# Node.net
KiCad netlist of a schematic drawn in EAGLE
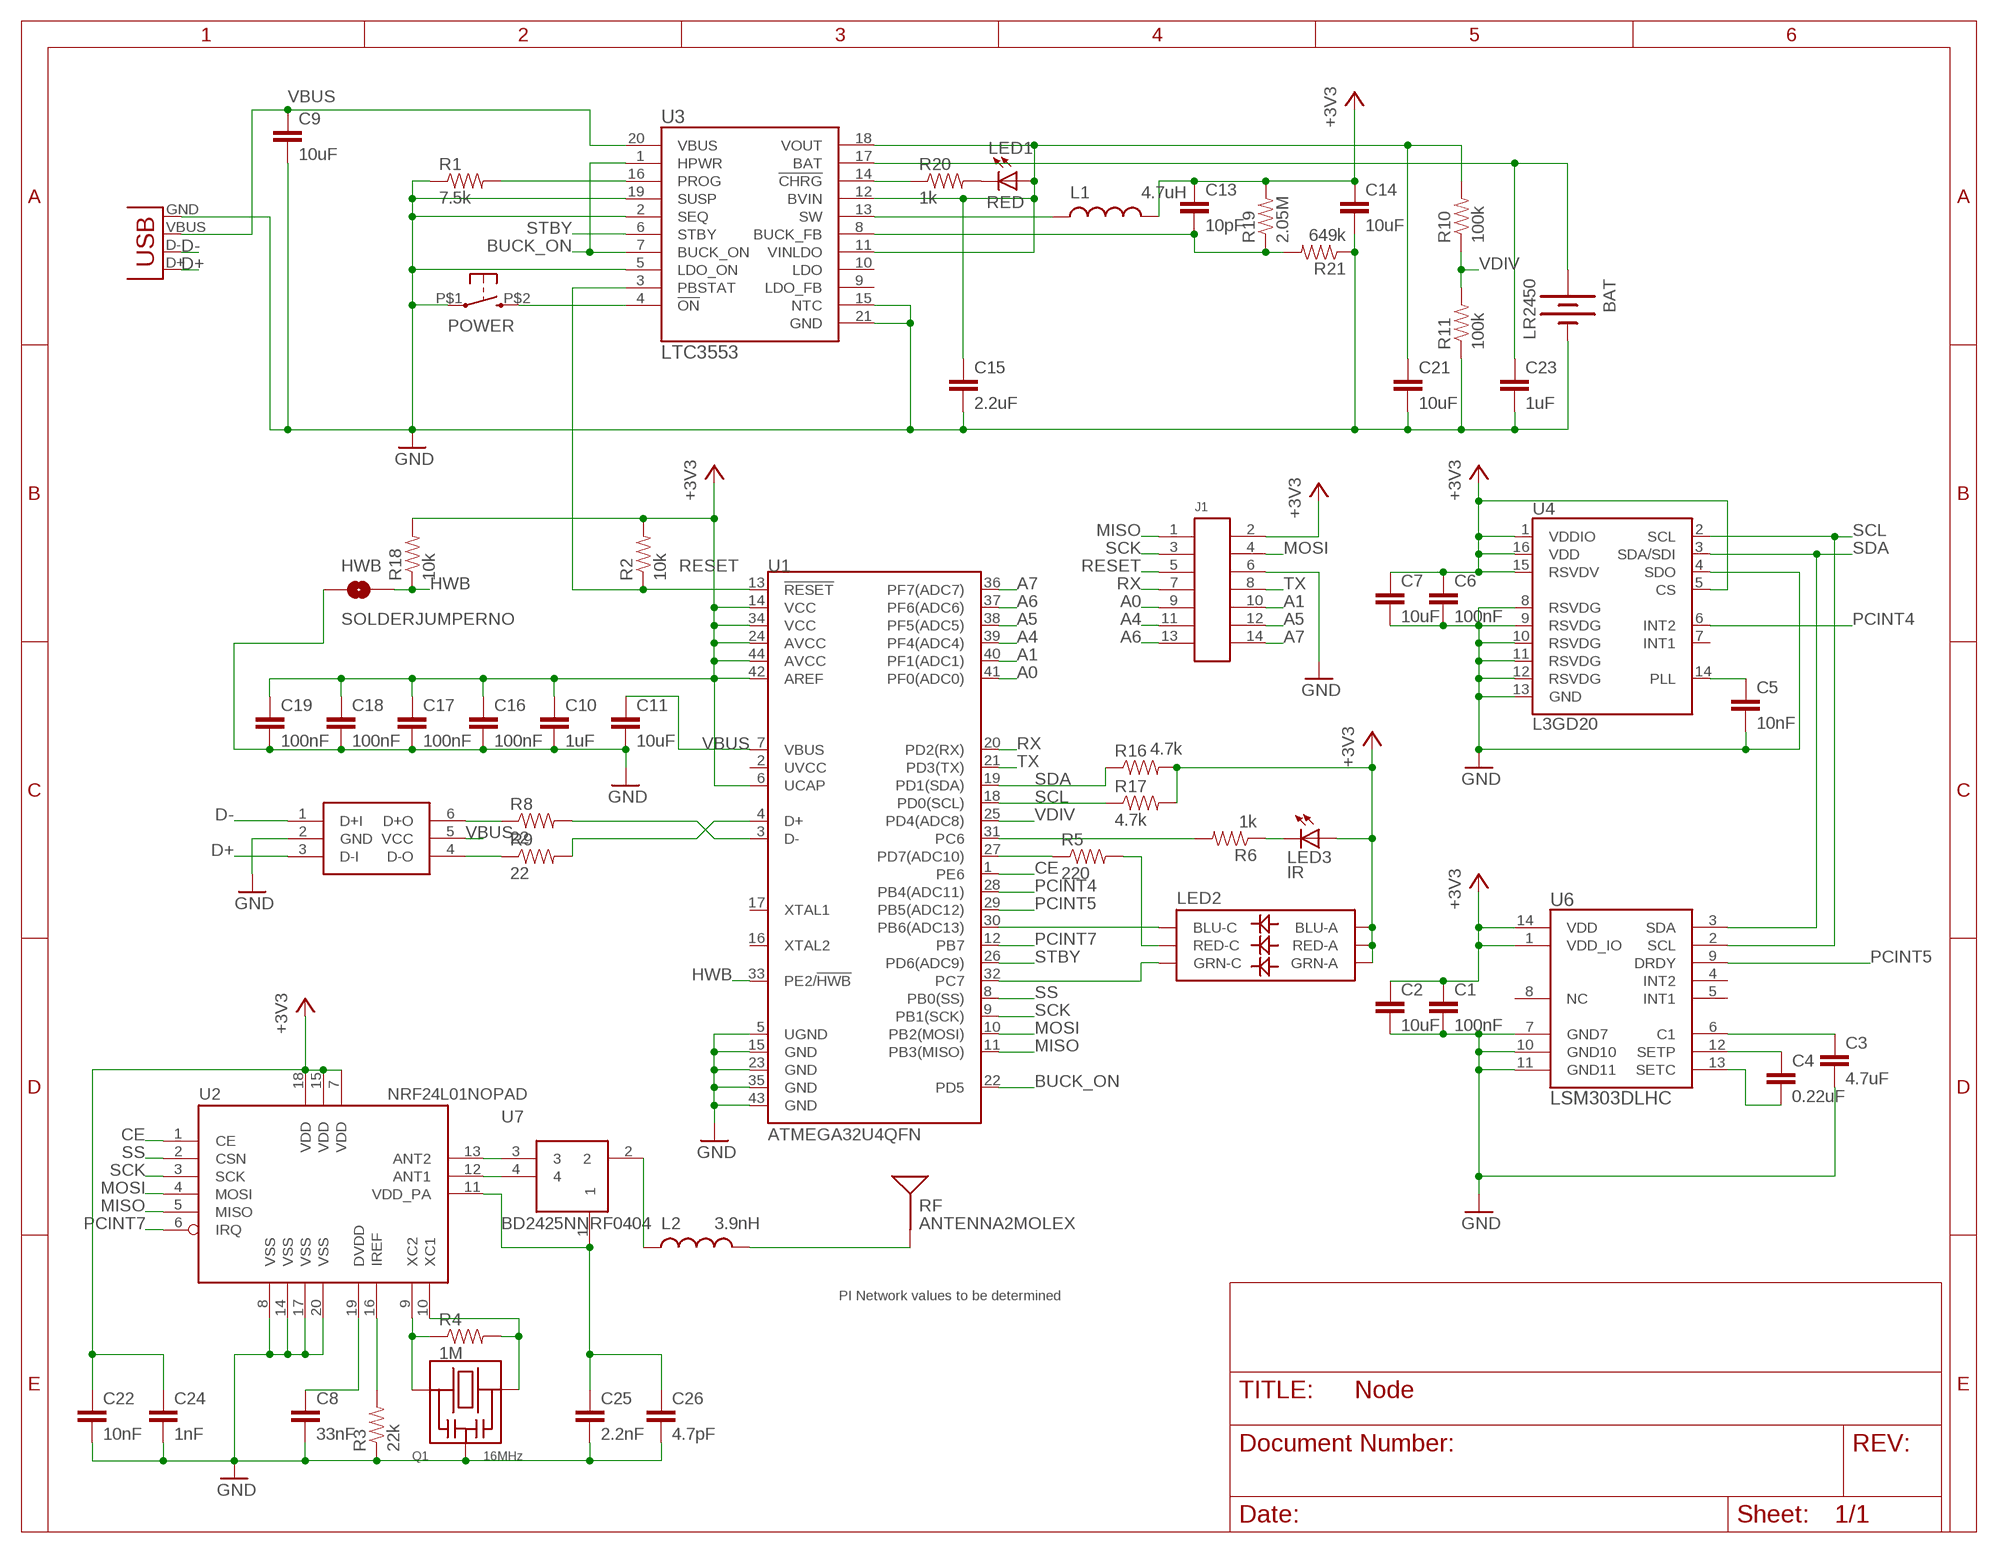
[diagram p0: schematic, sheet 1]

(export (version "E")
  (design (tool "Eeschema 10.0.6"))
  (components
    (comp (ref "BAT")
      (value "LR2450")
      (footprint "eagle-import:BATTCON_245MM_SLOT")
      (libsource (lib "eagle-import") (part "BATTERYSLOT"))
    )
    (comp (ref "C1")
      (value "100nF")
      (footprint "eagle-import:0402-CAP")
      (libsource (lib "eagle-import") (part "CAP0402-CAP"))
    )
    (comp (ref "C2")
      (value "10uF")
      (footprint "eagle-import:0603-CAP")
      (libsource (lib "eagle-import") (part "CAP0603-CAP"))
    )
    (comp (ref "C3")
      (value "4.7uF")
      (footprint "eagle-import:0603-CAP")
      (libsource (lib "eagle-import") (part "CAP0603-CAP"))
    )
    (comp (ref "C4")
      (value "0.22uF")
      (footprint "eagle-import:0402-CAP")
      (libsource (lib "eagle-import") (part "CAP0402-CAP"))
    )
    (comp (ref "C5")
      (value "10nF")
      (footprint "eagle-import:0402-CAP")
      (libsource (lib "eagle-import") (part "CAP0402-CAP"))
    )
    (comp (ref "C6")
      (value "100nF")
      (footprint "eagle-import:0402-CAP")
      (libsource (lib "eagle-import") (part "CAP0402-CAP"))
    )
    (comp (ref "C7")
      (value "10uF")
      (footprint "eagle-import:0603-CAP")
      (libsource (lib "eagle-import") (part "CAP0603-CAP"))
    )
    (comp (ref "C8")
      (value "33nF")
      (footprint "eagle-import:0402-CAP")
      (libsource (lib "eagle-import") (part "CAP0402-CAP"))
    )
    (comp (ref "C9")
      (value "10uF")
      (footprint "eagle-import:0603-CAP")
      (libsource (lib "eagle-import") (part "CAP0603-CAP"))
    )
    (comp (ref "C10")
      (value "1uF")
      (footprint "eagle-import:0402-CAP")
      (libsource (lib "eagle-import") (part "CAP0402-CAP"))
    )
    (comp (ref "C11")
      (value "10uF")
      (footprint "eagle-import:0603-CAP")
      (libsource (lib "eagle-import") (part "CAP0603-CAP"))
    )
    (comp (ref "C13")
      (value "10pF")
      (footprint "eagle-import:0402-CAP")
      (libsource (lib "eagle-import") (part "CAP0402-CAP"))
    )
    (comp (ref "C14")
      (value "10uF")
      (footprint "eagle-import:0603-CAP")
      (libsource (lib "eagle-import") (part "CAP0603-CAP"))
    )
    (comp (ref "C15")
      (value "2.2uF")
      (footprint "eagle-import:0402-CAP")
      (libsource (lib "eagle-import") (part "CAP0402-CAP"))
    )
    (comp (ref "C16")
      (value "100nF")
      (footprint "eagle-import:0402-CAP")
      (libsource (lib "eagle-import") (part "CAP0402-CAP"))
    )
    (comp (ref "C17")
      (value "100nF")
      (footprint "eagle-import:0402-CAP")
      (libsource (lib "eagle-import") (part "CAP0402-CAP"))
    )
    (comp (ref "C18")
      (value "100nF")
      (footprint "eagle-import:0402-CAP")
      (libsource (lib "eagle-import") (part "CAP0402-CAP"))
    )
    (comp (ref "C19")
      (value "100nF")
      (footprint "eagle-import:0402-CAP")
      (libsource (lib "eagle-import") (part "CAP0402-CAP"))
    )
    (comp (ref "C21")
      (value "10uF")
      (footprint "eagle-import:0603-CAP")
      (libsource (lib "eagle-import") (part "CAP0603-CAP"))
    )
    (comp (ref "C22")
      (value "10nF")
      (footprint "eagle-import:0402-CAP")
      (libsource (lib "eagle-import") (part "CAP0402-CAP"))
    )
    (comp (ref "C23")
      (value "1uF")
      (footprint "eagle-import:0402-CAP")
      (libsource (lib "eagle-import") (part "CAP0402-CAP"))
    )
    (comp (ref "C24")
      (value "1nF")
      (footprint "eagle-import:0402-CAP")
      (libsource (lib "eagle-import") (part "CAP0402-CAP"))
    )
    (comp (ref "C25")
      (value "2.2nF")
      (footprint "eagle-import:0402-CAP")
      (libsource (lib "eagle-import") (part "CAP0402-CAP"))
    )
    (comp (ref "C26")
      (value "4.7pF")
      (footprint "eagle-import:0402-CAP")
      (libsource (lib "eagle-import") (part "CAP0402-CAP"))
    )
    (comp (ref "HWB")
      (value "SOLDERJUMPERNO")
      (footprint "eagle-import:SJ_2S-NO")
      (libsource (lib "eagle-import") (part "SOLDERJUMPERNO"))
    )
    (comp (ref "J1")
      (value "DF12A3.0-14DS")
      (footprint "eagle-import:DF12A3.0-14DS")
      (libsource (lib "eagle-import") (part "DF12A3.0-14DS"))
    )
    (comp (ref "L1")
      (value "4.7uH")
      (footprint "eagle-import:VLS30")
      (libsource (lib "eagle-import") (part "INDUCTORVLS30"))
    )
    (comp (ref "L2")
      (value "3.9nH")
      (footprint "eagle-import:C0402")
      (libsource (lib "eagle-import") (part "INDUCTOR0402"))
    )
    (comp (ref "LED1")
      (value "RED")
      (footprint "eagle-import:LED-0603")
      (libsource (lib "eagle-import") (part "LED0603"))
    )
    (comp (ref "LED2")
      (value "LED-TRICOLOR-5050LED-TRICOLOR-0606")
      (footprint "eagle-import:0606")
      (libsource (lib "eagle-import") (part "LED-TRICOLOR-5050LED-TRICOLOR-0606"))
    )
    (comp (ref "LED3")
      (value "IR")
      (footprint "eagle-import:LED-0603")
      (libsource (lib "eagle-import") (part "LED0603"))
    )
    (comp (ref "POWER")
      (value "KSS")
      (footprint "eagle-import:KSS")
      (libsource (lib "eagle-import") (part "KSS"))
    )
    (comp (ref "Q1")
      (value "16MHz")
      (footprint "eagle-import:PRQC")
      (libsource (lib "eagle-import") (part "RESONATORPRQC"))
    )
    (comp (ref "R1")
      (value "7.5k")
      (footprint "eagle-import:0402-RES")
      (libsource (lib "eagle-import") (part "RESISTOR0402-RES"))
    )
    (comp (ref "R2")
      (value "10k")
      (footprint "eagle-import:0402-RES")
      (libsource (lib "eagle-import") (part "RESISTOR0402-RES"))
    )
    (comp (ref "R3")
      (value "22k")
      (footprint "eagle-import:0402-RES")
      (libsource (lib "eagle-import") (part "RESISTOR0402-RES"))
    )
    (comp (ref "R4")
      (value "1M")
      (footprint "eagle-import:0402-RES")
      (libsource (lib "eagle-import") (part "RESISTOR0402-RES"))
    )
    (comp (ref "R5")
      (value "220")
      (footprint "eagle-import:0402-RES")
      (libsource (lib "eagle-import") (part "RESISTOR0402-RES"))
    )
    (comp (ref "R6")
      (value "1k")
      (footprint "eagle-import:0402-RES")
      (libsource (lib "eagle-import") (part "RESISTOR0402-RES"))
    )
    (comp (ref "R8")
      (value "22")
      (footprint "eagle-import:0402-RES")
      (libsource (lib "eagle-import") (part "RESISTOR0402-RES"))
    )
    (comp (ref "R9")
      (value "22")
      (footprint "eagle-import:0402-RES")
      (libsource (lib "eagle-import") (part "RESISTOR0402-RES"))
    )
    (comp (ref "R10")
      (value "100k")
      (footprint "eagle-import:0402-RES")
      (libsource (lib "eagle-import") (part "RESISTOR0402-RES"))
    )
    (comp (ref "R11")
      (value "100k")
      (footprint "eagle-import:0402-RES")
      (libsource (lib "eagle-import") (part "RESISTOR0402-RES"))
    )
    (comp (ref "R16")
      (value "4.7k")
      (footprint "eagle-import:0402-RES")
      (libsource (lib "eagle-import") (part "RESISTOR0402-RES"))
    )
    (comp (ref "R17")
      (value "4.7k")
      (footprint "eagle-import:0402-RES")
      (libsource (lib "eagle-import") (part "RESISTOR0402-RES"))
    )
    (comp (ref "R18")
      (value "10k")
      (footprint "eagle-import:0402-RES")
      (libsource (lib "eagle-import") (part "RESISTOR0402-RES"))
    )
    (comp (ref "R19")
      (value "2.05M")
      (footprint "eagle-import:0402-RES")
      (libsource (lib "eagle-import") (part "RESISTOR0402-RES"))
    )
    (comp (ref "R20")
      (value "1k")
      (footprint "eagle-import:0402-RES")
      (libsource (lib "eagle-import") (part "RESISTOR0402-RES"))
    )
    (comp (ref "R21")
      (value "649k")
      (footprint "eagle-import:0402-RES")
      (libsource (lib "eagle-import") (part "RESISTOR0402-RES"))
    )
    (comp (ref "RF")
      (value "ANTENNA2MOLEX")
      (footprint "eagle-import:MOLEX2.4SMD")
      (libsource (lib "eagle-import") (part "ANTENNA2MOLEX"))
    )
    (comp (ref "U1")
      (value "ATMEGA32U4QFN")
      (footprint "eagle-import:QFN-44")
      (libsource (lib "eagle-import") (part "ATMEGA32U4QFN"))
    )
    (comp (ref "U2")
      (value "NRF24L01NOPAD")
      (footprint "eagle-import:QFN20-NOPAD")
      (libsource (lib "eagle-import") (part "NRF24L01NOPAD"))
    )
    (comp (ref "U3")
      (value "LTC3553")
      (footprint "eagle-import:QFN20-3X3")
      (libsource (lib "eagle-import") (part "LTC3553"))
    )
    (comp (ref "U4")
      (value "L3GD20")
      (footprint "eagle-import:LGA16-4X4")
      (libsource (lib "eagle-import") (part "L3GD20"))
    )
    (comp (ref "U6")
      (value "LSM303DLHC")
      (footprint "eagle-import:LGA14-3X5")
      (libsource (lib "eagle-import") (part "LSM303DLHC"))
    )
    (comp (ref "U7")
      (value "BD2425NNRF0404")
      (footprint "eagle-import:BD2425NNRF")
      (libsource (lib "eagle-import") (part "BD2425NNRF0404"))
    )
    (comp (ref "U9")
      (value "RCLAMP0502A")
      (footprint "eagle-import:SOT-666")
      (libsource (lib "eagle-import") (part "RCLAMP0502A"))
    )
    (comp (ref "X1")
      (value "USB-FCI")
      (footprint "eagle-import:USB-MICROB-FCI")
      (libsource (lib "eagle-import") (part "USB-FCI"))
    )
  )
  (nets
    (net (code "1") (name "+3V3") (class "Default")
      (node (ref "C1") (pin "1") (pinfunction "1_1") (pintype "passive"))
      (node (ref "C10") (pin "1") (pinfunction "1_1") (pintype "passive"))
      (node (ref "C13") (pin "1") (pinfunction "1_1") (pintype "passive"))
      (node (ref "C14") (pin "1") (pinfunction "1_1") (pintype "passive"))
      (node (ref "C16") (pin "1") (pinfunction "1_1") (pintype "passive"))
      (node (ref "C17") (pin "1") (pinfunction "1_1") (pintype "passive"))
      (node (ref "C18") (pin "1") (pinfunction "1_1") (pintype "passive"))
      (node (ref "C19") (pin "1") (pinfunction "1_1") (pintype "passive"))
      (node (ref "C2") (pin "1") (pinfunction "1_1") (pintype "passive"))
      (node (ref "C22") (pin "1") (pinfunction "1_1") (pintype "passive"))
      (node (ref "C24") (pin "1") (pinfunction "1_1") (pintype "passive"))
      (node (ref "C6") (pin "1") (pinfunction "1_1") (pintype "passive"))
      (node (ref "C7") (pin "1") (pinfunction "1_1") (pintype "passive"))
      (node (ref "J1") (pin "2") (pinfunction "2_2") (pintype "bidirectional"))
      (node (ref "L1") (pin "2") (pinfunction "2_2") (pintype "passive"))
      (node (ref "LED2") (pin "4") (pinfunction "BLU-A_4") (pintype "bidirectional"))
      (node (ref "LED2") (pin "5") (pinfunction "RED-A_5") (pintype "bidirectional"))
      (node (ref "LED2") (pin "6") (pinfunction "GRN-A_6") (pintype "bidirectional"))
      (node (ref "LED3") (pin "A") (pinfunction "A_A") (pintype "passive"))
      (node (ref "R16") (pin "2") (pinfunction "2_2") (pintype "passive"))
      (node (ref "R17") (pin "2") (pinfunction "2_2") (pintype "passive"))
      (node (ref "R18") (pin "2") (pinfunction "2_2") (pintype "passive"))
      (node (ref "R19") (pin "2") (pinfunction "2_2") (pintype "passive"))
      (node (ref "R2") (pin "2") (pinfunction "2_2") (pintype "passive"))
      (node (ref "U1") (pin "14") (pinfunction "VCC_14") (pintype "bidirectional"))
      (node (ref "U1") (pin "24") (pinfunction "AVCC_24") (pintype "bidirectional"))
      (node (ref "U1") (pin "34") (pinfunction "VCC_34") (pintype "bidirectional"))
      (node (ref "U1") (pin "42") (pinfunction "AREF_42") (pintype "bidirectional"))
      (node (ref "U1") (pin "44") (pinfunction "AVCC_44") (pintype "bidirectional"))
      (node (ref "U1") (pin "6") (pinfunction "UCAP_6") (pintype "bidirectional"))
      (node (ref "U2") (pin "15") (pinfunction "VDD_15") (pintype "power_in"))
      (node (ref "U2") (pin "18") (pinfunction "VDD_18") (pintype "power_in"))
      (node (ref "U2") (pin "7") (pinfunction "VDD_7") (pintype "power_in"))
      (node (ref "U4") (pin "1") (pinfunction "VDDIO_1") (pintype "bidirectional"))
      (node (ref "U4") (pin "15") (pinfunction "RSVDV_15") (pintype "bidirectional"))
      (node (ref "U4") (pin "16") (pinfunction "VDD_16") (pintype "bidirectional"))
      (node (ref "U4") (pin "5") (pinfunction "CS_5") (pintype "bidirectional"))
      (node (ref "U6") (pin "1") (pinfunction "VDD_IO_1") (pintype "bidirectional"))
      (node (ref "U6") (pin "14") (pinfunction "VDD_14") (pintype "bidirectional"))
    )
    (net (code "2") (name "/A0") (class "Default")
      (node (ref "J1") (pin "9") (pinfunction "9_9") (pintype "bidirectional"))
      (node (ref "U1") (pin "41") (pinfunction "PF0(ADC0)_41") (pintype "bidirectional"))
    )
    (net (code "3") (name "/A1") (class "Default")
      (node (ref "J1") (pin "10") (pinfunction "10_10") (pintype "bidirectional"))
      (node (ref "U1") (pin "40") (pinfunction "PF1(ADC1)_40") (pintype "bidirectional"))
    )
    (net (code "4") (name "/A4") (class "Default")
      (node (ref "J1") (pin "11") (pinfunction "11_11") (pintype "bidirectional"))
      (node (ref "U1") (pin "39") (pinfunction "PF4(ADC4)_39") (pintype "bidirectional"))
    )
    (net (code "5") (name "/A5") (class "Default")
      (node (ref "J1") (pin "12") (pinfunction "12_12") (pintype "bidirectional"))
      (node (ref "U1") (pin "38") (pinfunction "PF5(ADC5)_38") (pintype "bidirectional"))
    )
    (net (code "6") (name "/A6") (class "Default")
      (node (ref "J1") (pin "13") (pinfunction "13_13") (pintype "bidirectional"))
      (node (ref "U1") (pin "37") (pinfunction "PF6(ADC6)_37") (pintype "bidirectional"))
    )
    (net (code "7") (name "/A7") (class "Default")
      (node (ref "J1") (pin "14") (pinfunction "14_14") (pintype "bidirectional"))
      (node (ref "U1") (pin "36") (pinfunction "PF7(ADC7)_36") (pintype "bidirectional"))
    )
    (net (code "8") (name "/BUCK_ON") (class "Default")
      (node (ref "U1") (pin "22") (pinfunction "PD5_22") (pintype "bidirectional"))
      (node (ref "U3") (pin "1") (pinfunction "HPWR_1") (pintype "bidirectional"))
      (node (ref "U3") (pin "7") (pinfunction "BUCK_ON_7") (pintype "bidirectional"))
    )
    (net (code "9") (name "/CE") (class "Default")
      (node (ref "U1") (pin "1") (pinfunction "PE6_1") (pintype "bidirectional"))
      (node (ref "U2") (pin "1") (pinfunction "CE_1") (pintype "input"))
    )
    (net (code "10") (name "/D+") (class "Default")
      (node (ref "U9") (pin "3") (pinfunction "D-I_3") (pintype "bidirectional"))
      (node (ref "X1") (pin "D+") (pinfunction "D+_D+") (pintype "bidirectional"))
    )
    (net (code "11") (name "/D-") (class "Default")
      (node (ref "U9") (pin "1") (pinfunction "D+I_1") (pintype "bidirectional"))
      (node (ref "X1") (pin "D-") (pinfunction "D-_D-") (pintype "bidirectional"))
    )
    (net (code "12") (name "/HWB") (class "Default")
      (node (ref "HWB") (pin "2") (pinfunction "2_2") (pintype "passive"))
      (node (ref "R18") (pin "1") (pinfunction "1_1") (pintype "passive"))
      (node (ref "U1") (pin "33") (pinfunction "PE2/~{HWB}_33") (pintype "bidirectional"))
    )
    (net (code "13") (name "/MISO") (class "Default")
      (node (ref "J1") (pin "1") (pinfunction "1_1") (pintype "bidirectional"))
      (node (ref "U1") (pin "11") (pinfunction "PB3(MISO)_11") (pintype "bidirectional"))
      (node (ref "U2") (pin "5") (pinfunction "MISO_5") (pintype "output"))
    )
    (net (code "14") (name "/MOSI") (class "Default")
      (node (ref "J1") (pin "4") (pinfunction "4_4") (pintype "bidirectional"))
      (node (ref "U1") (pin "10") (pinfunction "PB2(MOSI)_10") (pintype "bidirectional"))
      (node (ref "U2") (pin "4") (pinfunction "MOSI_4") (pintype "input"))
    )
    (net (code "15") (name "/PCINT4") (class "Default")
      (node (ref "U1") (pin "28") (pinfunction "PB4(ADC11)_28") (pintype "bidirectional"))
      (node (ref "U4") (pin "6") (pinfunction "INT2_6") (pintype "bidirectional"))
    )
    (net (code "16") (name "/PCINT5") (class "Default")
      (node (ref "U1") (pin "29") (pinfunction "PB5(ADC12)_29") (pintype "bidirectional"))
      (node (ref "U6") (pin "9") (pinfunction "DRDY_9") (pintype "bidirectional"))
    )
    (net (code "17") (name "/PCINT7") (class "Default")
      (node (ref "U1") (pin "12") (pinfunction "PB7_12") (pintype "bidirectional"))
      (node (ref "U2") (pin "6") (pinfunction "IRQ_6") (pintype "output"))
    )
    (net (code "18") (name "/RESET") (class "Default")
      (node (ref "J1") (pin "5") (pinfunction "5_5") (pintype "bidirectional"))
      (node (ref "R2") (pin "1") (pinfunction "1_1") (pintype "passive"))
      (node (ref "U1") (pin "13") (pinfunction "~{RESET}_13") (pintype "bidirectional"))
      (node (ref "U3") (pin "3") (pinfunction "PBSTAT_3") (pintype "bidirectional"))
    )
    (net (code "19") (name "/RX") (class "Default")
      (node (ref "J1") (pin "7") (pinfunction "7_7") (pintype "bidirectional"))
      (node (ref "U1") (pin "20") (pinfunction "PD2(RX)_20") (pintype "bidirectional"))
    )
    (net (code "20") (name "/SCK") (class "Default")
      (node (ref "J1") (pin "3") (pinfunction "3_3") (pintype "bidirectional"))
      (node (ref "U1") (pin "9") (pinfunction "PB1(SCK)_9") (pintype "bidirectional"))
      (node (ref "U2") (pin "3") (pinfunction "SCK_3") (pintype "input"))
    )
    (net (code "21") (name "/SCL") (class "Default")
      (node (ref "R17") (pin "1") (pinfunction "1_1") (pintype "passive"))
      (node (ref "U1") (pin "18") (pinfunction "PD0(SCL)_18") (pintype "bidirectional"))
      (node (ref "U4") (pin "2") (pinfunction "SCL_2") (pintype "bidirectional"))
      (node (ref "U6") (pin "2") (pinfunction "SCL_2") (pintype "bidirectional"))
    )
    (net (code "22") (name "/SDA") (class "Default")
      (node (ref "R16") (pin "1") (pinfunction "1_1") (pintype "passive"))
      (node (ref "U1") (pin "19") (pinfunction "PD1(SDA)_19") (pintype "bidirectional"))
      (node (ref "U4") (pin "3") (pinfunction "SDA/SDI_3") (pintype "bidirectional"))
      (node (ref "U6") (pin "3") (pinfunction "SDA_3") (pintype "bidirectional"))
    )
    (net (code "23") (name "/SS") (class "Default")
      (node (ref "U1") (pin "8") (pinfunction "PB0(SS)_8") (pintype "bidirectional"))
      (node (ref "U2") (pin "2") (pinfunction "CSN_2") (pintype "input"))
    )
    (net (code "24") (name "/STBY") (class "Default")
      (node (ref "U1") (pin "26") (pinfunction "PD6(ADC9)_26") (pintype "bidirectional"))
      (node (ref "U3") (pin "6") (pinfunction "STBY_6") (pintype "bidirectional"))
    )
    (net (code "25") (name "/TX") (class "Default")
      (node (ref "J1") (pin "8") (pinfunction "8_8") (pintype "bidirectional"))
      (node (ref "U1") (pin "21") (pinfunction "PD3(TX)_21") (pintype "bidirectional"))
    )
    (net (code "26") (name "/VBUS") (class "Default")
      (node (ref "C11") (pin "1") (pinfunction "1_1") (pintype "passive"))
      (node (ref "C9") (pin "1") (pinfunction "1_1") (pintype "passive"))
      (node (ref "U1") (pin "7") (pinfunction "VBUS_7") (pintype "bidirectional"))
      (node (ref "U3") (pin "20") (pinfunction "VBUS_20") (pintype "bidirectional"))
      (node (ref "U9") (pin "5") (pinfunction "VCC_5") (pintype "bidirectional"))
      (node (ref "X1") (pin "VBUS") (pinfunction "VBUS_VBUS") (pintype "bidirectional"))
    )
    (net (code "27") (name "/VDIV") (class "Default")
      (node (ref "R10") (pin "1") (pinfunction "1_1") (pintype "passive"))
      (node (ref "R11") (pin "2") (pinfunction "2_2") (pintype "passive"))
      (node (ref "U1") (pin "25") (pinfunction "PD4(ADC8)_25") (pintype "bidirectional"))
    )
    (net (code "28") (name "GND") (class "Default")
      (node (ref "BAT") (pin "GND") (pinfunction "-_GND") (pintype "power_in"))
      (node (ref "C1") (pin "2") (pinfunction "2_2") (pintype "passive"))
      (node (ref "C10") (pin "2") (pinfunction "2_2") (pintype "passive"))
      (node (ref "C11") (pin "2") (pinfunction "2_2") (pintype "passive"))
      (node (ref "C14") (pin "2") (pinfunction "2_2") (pintype "passive"))
      (node (ref "C15") (pin "2") (pinfunction "2_2") (pintype "passive"))
      (node (ref "C16") (pin "2") (pinfunction "2_2") (pintype "passive"))
      (node (ref "C17") (pin "2") (pinfunction "2_2") (pintype "passive"))
      (node (ref "C18") (pin "2") (pinfunction "2_2") (pintype "passive"))
      (node (ref "C19") (pin "2") (pinfunction "2_2") (pintype "passive"))
      (node (ref "C2") (pin "2") (pinfunction "2_2") (pintype "passive"))
      (node (ref "C21") (pin "2") (pinfunction "2_2") (pintype "passive"))
      (node (ref "C22") (pin "2") (pinfunction "2_2") (pintype "passive"))
      (node (ref "C23") (pin "2") (pinfunction "2_2") (pintype "passive"))
      (node (ref "C24") (pin "2") (pinfunction "2_2") (pintype "passive"))
      (node (ref "C25") (pin "2") (pinfunction "2_2") (pintype "passive"))
      (node (ref "C26") (pin "2") (pinfunction "2_2") (pintype "passive"))
      (node (ref "C3") (pin "2") (pinfunction "2_2") (pintype "passive"))
      (node (ref "C5") (pin "2") (pinfunction "2_2") (pintype "passive"))
      (node (ref "C6") (pin "2") (pinfunction "2_2") (pintype "passive"))
      (node (ref "C7") (pin "2") (pinfunction "2_2") (pintype "passive"))
      (node (ref "C8") (pin "2") (pinfunction "2_2") (pintype "passive"))
      (node (ref "C9") (pin "2") (pinfunction "2_2") (pintype "passive"))
      (node (ref "HWB") (pin "1") (pinfunction "1_1") (pintype "passive"))
      (node (ref "J1") (pin "6") (pinfunction "6_6") (pintype "bidirectional"))
      (node (ref "POWER") (pin "P$1") (pinfunction "1_P$1") (pintype "passive"))
      (node (ref "Q1") (pin "P$2") (pinfunction "GND_P$2") (pintype "power_in"))
      (node (ref "R1") (pin "1") (pinfunction "1_1") (pintype "passive"))
      (node (ref "R11") (pin "1") (pinfunction "1_1") (pintype "passive"))
      (node (ref "R21") (pin "1") (pinfunction "1_1") (pintype "passive"))
      (node (ref "R3") (pin "1") (pinfunction "1_1") (pintype "passive"))
      (node (ref "U1") (pin "15") (pinfunction "GND_15") (pintype "bidirectional"))
      (node (ref "U1") (pin "23") (pinfunction "GND_23") (pintype "bidirectional"))
      (node (ref "U1") (pin "35") (pinfunction "GND_35") (pintype "bidirectional"))
      (node (ref "U1") (pin "43") (pinfunction "GND_43") (pintype "bidirectional"))
      (node (ref "U1") (pin "5") (pinfunction "UGND_5") (pintype "bidirectional"))
      (node (ref "U2") (pin "14") (pinfunction "VSS_14") (pintype "power_in"))
      (node (ref "U2") (pin "17") (pinfunction "VSS_17") (pintype "power_in"))
      (node (ref "U2") (pin "20") (pinfunction "VSS_20") (pintype "power_in"))
      (node (ref "U2") (pin "8") (pinfunction "VSS_8") (pintype "power_in"))
      (node (ref "U3") (pin "15") (pinfunction "NTC_15") (pintype "bidirectional"))
      (node (ref "U3") (pin "19") (pinfunction "SUSP_19") (pintype "bidirectional"))
      (node (ref "U3") (pin "2") (pinfunction "SEQ_2") (pintype "bidirectional"))
      (node (ref "U3") (pin "21") (pinfunction "GND_21") (pintype "bidirectional"))
      (node (ref "U3") (pin "5") (pinfunction "LDO_ON_5") (pintype "bidirectional"))
      (node (ref "U4") (pin "10") (pinfunction "RSVDG_10") (pintype "bidirectional"))
      (node (ref "U4") (pin "11") (pinfunction "RSVDG_11") (pintype "bidirectional"))
      (node (ref "U4") (pin "12") (pinfunction "RSVDG_12") (pintype "bidirectional"))
      (node (ref "U4") (pin "13") (pinfunction "GND_13") (pintype "bidirectional"))
      (node (ref "U4") (pin "4") (pinfunction "SDO_4") (pintype "bidirectional"))
      (node (ref "U4") (pin "8") (pinfunction "RSVDG_8") (pintype "bidirectional"))
      (node (ref "U4") (pin "9") (pinfunction "RSVDG_9") (pintype "bidirectional"))
      (node (ref "U6") (pin "10") (pinfunction "GND10_10") (pintype "bidirectional"))
      (node (ref "U6") (pin "11") (pinfunction "GND11_11") (pintype "bidirectional"))
      (node (ref "U6") (pin "7") (pinfunction "GND7_7") (pintype "bidirectional"))
      (node (ref "U9") (pin "2") (pinfunction "GND_2") (pintype "bidirectional"))
      (node (ref "X1") (pin "GND") (pinfunction "GND_GND") (pintype "bidirectional"))
    )
    (net (code "29") (name "Net-(L2-Pad1)") (class "Default")
      (node (ref "L2") (pin "1") (pinfunction "1_1") (pintype "passive"))
      (node (ref "U7") (pin "2") (pinfunction "2_2") (pintype "bidirectional"))
    )
    (net (code "30") (name "Net-(LED1-PadC)") (class "Default")
      (node (ref "LED1") (pin "C") (pinfunction "C_C") (pintype "passive"))
      (node (ref "R20") (pin "2") (pinfunction "2_2") (pintype "passive"))
    )
    (net (code "31") (name "Net-(LED2-BLU-C)") (class "Default")
      (node (ref "LED2") (pin "1") (pinfunction "BLU-C_1") (pintype "bidirectional"))
      (node (ref "U1") (pin "30") (pinfunction "PB6(ADC13)_30") (pintype "bidirectional"))
    )
    (net (code "32") (name "Net-(LED2-GRN-C)") (class "Default")
      (node (ref "LED2") (pin "3") (pinfunction "GRN-C_3") (pintype "bidirectional"))
      (node (ref "U1") (pin "32") (pinfunction "PC7_32") (pintype "bidirectional"))
    )
    (net (code "33") (name "Net-(LED2-RED-C)") (class "Default")
      (node (ref "LED2") (pin "2") (pinfunction "RED-C_2") (pintype "bidirectional"))
      (node (ref "R5") (pin "2") (pinfunction "2_2") (pintype "passive"))
    )
    (net (code "34") (name "Net-(LED3-PadC)") (class "Default")
      (node (ref "LED3") (pin "C") (pinfunction "C_C") (pintype "passive"))
      (node (ref "R6") (pin "1") (pinfunction "1_1") (pintype "passive"))
    )
    (net (code "35") (name "Net-(POWER-3)") (class "Default")
      (node (ref "POWER") (pin "P$2") (pinfunction "3_P$2") (pintype "passive"))
      (node (ref "U3") (pin "4") (pinfunction "~{ON}_4") (pintype "bidirectional"))
    )
    (net (code "36") (name "Net-(Q1-1)") (class "Default")
      (node (ref "Q1") (pin "P$1") (pinfunction "1_P$1") (pintype "bidirectional"))
      (node (ref "R4") (pin "1") (pinfunction "1_1") (pintype "passive"))
      (node (ref "U2") (pin "9") (pinfunction "XC2_9") (pintype "input"))
    )
    (net (code "37") (name "Net-(Q1-2)") (class "Default")
      (node (ref "Q1") (pin "P$3") (pinfunction "2_P$3") (pintype "bidirectional"))
      (node (ref "R4") (pin "2") (pinfunction "2_2") (pintype "passive"))
      (node (ref "U2") (pin "10") (pinfunction "XC1_10") (pintype "input"))
    )
    (net (code "38") (name "Net-(RF-SIGNAL)") (class "Default")
      (node (ref "L2") (pin "2") (pinfunction "2_2") (pintype "passive"))
      (node (ref "RF") (pin "FEED") (pinfunction "SIGNAL_FEED") (pintype "bidirectional"))
    )
    (net (code "39") (name "Net-(U1-D+)") (class "Default")
      (node (ref "R9") (pin "2") (pinfunction "2_2") (pintype "passive"))
      (node (ref "U1") (pin "4") (pinfunction "D+_4") (pintype "bidirectional"))
    )
    (net (code "40") (name "Net-(U1-D-)") (class "Default")
      (node (ref "R8") (pin "2") (pinfunction "2_2") (pintype "passive"))
      (node (ref "U1") (pin "3") (pinfunction "D-_3") (pintype "bidirectional"))
    )
    (net (code "41") (name "Net-(U1-PC6)") (class "Default")
      (node (ref "R6") (pin "2") (pinfunction "2_2") (pintype "passive"))
      (node (ref "U1") (pin "31") (pinfunction "PC6_31") (pintype "bidirectional"))
    )
    (net (code "42") (name "Net-(U1-PD7(ADC10))") (class "Default")
      (node (ref "R5") (pin "1") (pinfunction "1_1") (pintype "passive"))
      (node (ref "U1") (pin "27") (pinfunction "PD7(ADC10)_27") (pintype "bidirectional"))
    )
    (net (code "43") (name "Net-(U2-ANT1)") (class "Default")
      (node (ref "U2") (pin "12") (pinfunction "ANT1_12") (pintype "output"))
      (node (ref "U7") (pin "4") (pinfunction "4_4") (pintype "bidirectional"))
    )
    (net (code "44") (name "Net-(U2-ANT2)") (class "Default")
      (node (ref "U2") (pin "13") (pinfunction "ANT2_13") (pintype "output"))
      (node (ref "U7") (pin "3") (pinfunction "3_3") (pintype "bidirectional"))
    )
    (net (code "45") (name "Net-(U2-DVDD)") (class "Default")
      (node (ref "C8") (pin "1") (pinfunction "1_1") (pintype "passive"))
      (node (ref "U2") (pin "19") (pinfunction "DVDD_19") (pintype "power_in"))
    )
    (net (code "46") (name "Net-(U2-IREF)") (class "Default")
      (node (ref "R3") (pin "2") (pinfunction "2_2") (pintype "passive"))
      (node (ref "U2") (pin "16") (pinfunction "IREF_16") (pintype "input"))
    )
    (net (code "47") (name "Net-(U2-VDD_PA)") (class "Default")
      (node (ref "C25") (pin "1") (pinfunction "1_1") (pintype "passive"))
      (node (ref "C26") (pin "1") (pinfunction "1_1") (pintype "passive"))
      (node (ref "U2") (pin "11") (pinfunction "VDD_PA_11") (pintype "power_in"))
      (node (ref "U7") (pin "1") (pinfunction "1_1") (pintype "bidirectional"))
    )
    (net (code "48") (name "Net-(U3-BAT)") (class "Default")
      (node (ref "BAT") (pin "+1") (pinfunction "+_+1") (pintype "power_in"))
      (node (ref "BAT") (pin "+2") (pinfunction "+_+2") (pintype "power_in"))
      (node (ref "BAT") (pin "+3") (pinfunction "+_+3") (pintype "power_in"))
      (node (ref "BAT") (pin "+4") (pinfunction "+_+4") (pintype "power_in"))
      (node (ref "C23") (pin "1") (pinfunction "1_1") (pintype "passive"))
      (node (ref "U3") (pin "17") (pinfunction "BAT_17") (pintype "bidirectional"))
    )
    (net (code "49") (name "Net-(U3-BUCK_FB)") (class "Default")
      (node (ref "C13") (pin "2") (pinfunction "2_2") (pintype "passive"))
      (node (ref "R19") (pin "1") (pinfunction "1_1") (pintype "passive"))
      (node (ref "R21") (pin "2") (pinfunction "2_2") (pintype "passive"))
      (node (ref "U3") (pin "8") (pinfunction "BUCK_FB_8") (pintype "bidirectional"))
    )
    (net (code "50") (name "Net-(U3-BVIN)") (class "Default")
      (node (ref "C15") (pin "1") (pinfunction "1_1") (pintype "passive"))
      (node (ref "C21") (pin "1") (pinfunction "1_1") (pintype "passive"))
      (node (ref "LED1") (pin "A") (pinfunction "A_A") (pintype "passive"))
      (node (ref "R10") (pin "2") (pinfunction "2_2") (pintype "passive"))
      (node (ref "U3") (pin "11") (pinfunction "VINLDO_11") (pintype "bidirectional"))
      (node (ref "U3") (pin "12") (pinfunction "BVIN_12") (pintype "bidirectional"))
      (node (ref "U3") (pin "18") (pinfunction "VOUT_18") (pintype "bidirectional"))
    )
    (net (code "51") (name "Net-(U3-PROG)") (class "Default")
      (node (ref "R1") (pin "2") (pinfunction "2_2") (pintype "passive"))
      (node (ref "U3") (pin "16") (pinfunction "PROG_16") (pintype "bidirectional"))
    )
    (net (code "52") (name "Net-(U3-SW)") (class "Default")
      (node (ref "L1") (pin "1") (pinfunction "1_1") (pintype "passive"))
      (node (ref "U3") (pin "13") (pinfunction "SW_13") (pintype "bidirectional"))
    )
    (net (code "53") (name "Net-(U3-~{CHRG})") (class "Default")
      (node (ref "R20") (pin "1") (pinfunction "1_1") (pintype "passive"))
      (node (ref "U3") (pin "14") (pinfunction "~{CHRG}_14") (pintype "bidirectional"))
    )
    (net (code "54") (name "Net-(U4-PLL)") (class "Default")
      (node (ref "C5") (pin "1") (pinfunction "1_1") (pintype "passive"))
      (node (ref "U4") (pin "14") (pinfunction "PLL_14") (pintype "bidirectional"))
    )
    (net (code "55") (name "Net-(U6-C1)") (class "Default")
      (node (ref "C3") (pin "1") (pinfunction "1_1") (pintype "passive"))
      (node (ref "U6") (pin "6") (pinfunction "C1_6") (pintype "bidirectional"))
    )
    (net (code "56") (name "Net-(U6-SETC)") (class "Default")
      (node (ref "C4") (pin "2") (pinfunction "2_2") (pintype "passive"))
      (node (ref "U6") (pin "13") (pinfunction "SETC_13") (pintype "bidirectional"))
    )
    (net (code "57") (name "Net-(U6-SETP)") (class "Default")
      (node (ref "C4") (pin "1") (pinfunction "1_1") (pintype "passive"))
      (node (ref "U6") (pin "12") (pinfunction "SETP_12") (pintype "bidirectional"))
    )
    (net (code "58") (name "Net-(U9-D+O)") (class "Default")
      (node (ref "R8") (pin "1") (pinfunction "1_1") (pintype "passive"))
      (node (ref "U9") (pin "6") (pinfunction "D+O_6") (pintype "bidirectional"))
    )
    (net (code "59") (name "Net-(U9-D-O)") (class "Default")
      (node (ref "R9") (pin "1") (pinfunction "1_1") (pintype "passive"))
      (node (ref "U9") (pin "4") (pinfunction "D-O_4") (pintype "bidirectional"))
    )
    (net (code "60") (name "unconnected-(U1-UVCC-Pad2)") (class "Default")
      (node (ref "U1") (pin "2") (pinfunction "UVCC_2") (pintype "bidirectional"))
    )
    (net (code "61") (name "unconnected-(U1-XTAL1-Pad17)") (class "Default")
      (node (ref "U1") (pin "17") (pinfunction "XTAL1_17") (pintype "bidirectional"))
    )
    (net (code "62") (name "unconnected-(U1-XTAL2-Pad16)") (class "Default")
      (node (ref "U1") (pin "16") (pinfunction "XTAL2_16") (pintype "bidirectional"))
    )
    (net (code "63") (name "unconnected-(U3-LDO-Pad10)") (class "Default")
      (node (ref "U3") (pin "10") (pinfunction "LDO_10") (pintype "bidirectional"))
    )
    (net (code "64") (name "unconnected-(U3-LDO_FB-Pad9)") (class "Default")
      (node (ref "U3") (pin "9") (pinfunction "LDO_FB_9") (pintype "bidirectional"))
    )
    (net (code "65") (name "unconnected-(U4-INT1-Pad7)") (class "Default")
      (node (ref "U4") (pin "7") (pinfunction "INT1_7") (pintype "bidirectional"))
    )
    (net (code "66") (name "unconnected-(U6-INT1-Pad5)") (class "Default")
      (node (ref "U6") (pin "5") (pinfunction "INT1_5") (pintype "bidirectional"))
    )
    (net (code "67") (name "unconnected-(U6-INT2-Pad4)") (class "Default")
      (node (ref "U6") (pin "4") (pinfunction "INT2_4") (pintype "bidirectional"))
    )
    (net (code "68") (name "unconnected-(U6-NC-Pad8)") (class "Default")
      (node (ref "U6") (pin "8") (pinfunction "NC_8") (pintype "bidirectional"))
    )
  )
)
